# OTOsenseShield.net
KiCad netlist of a schematic drawn in EAGLE
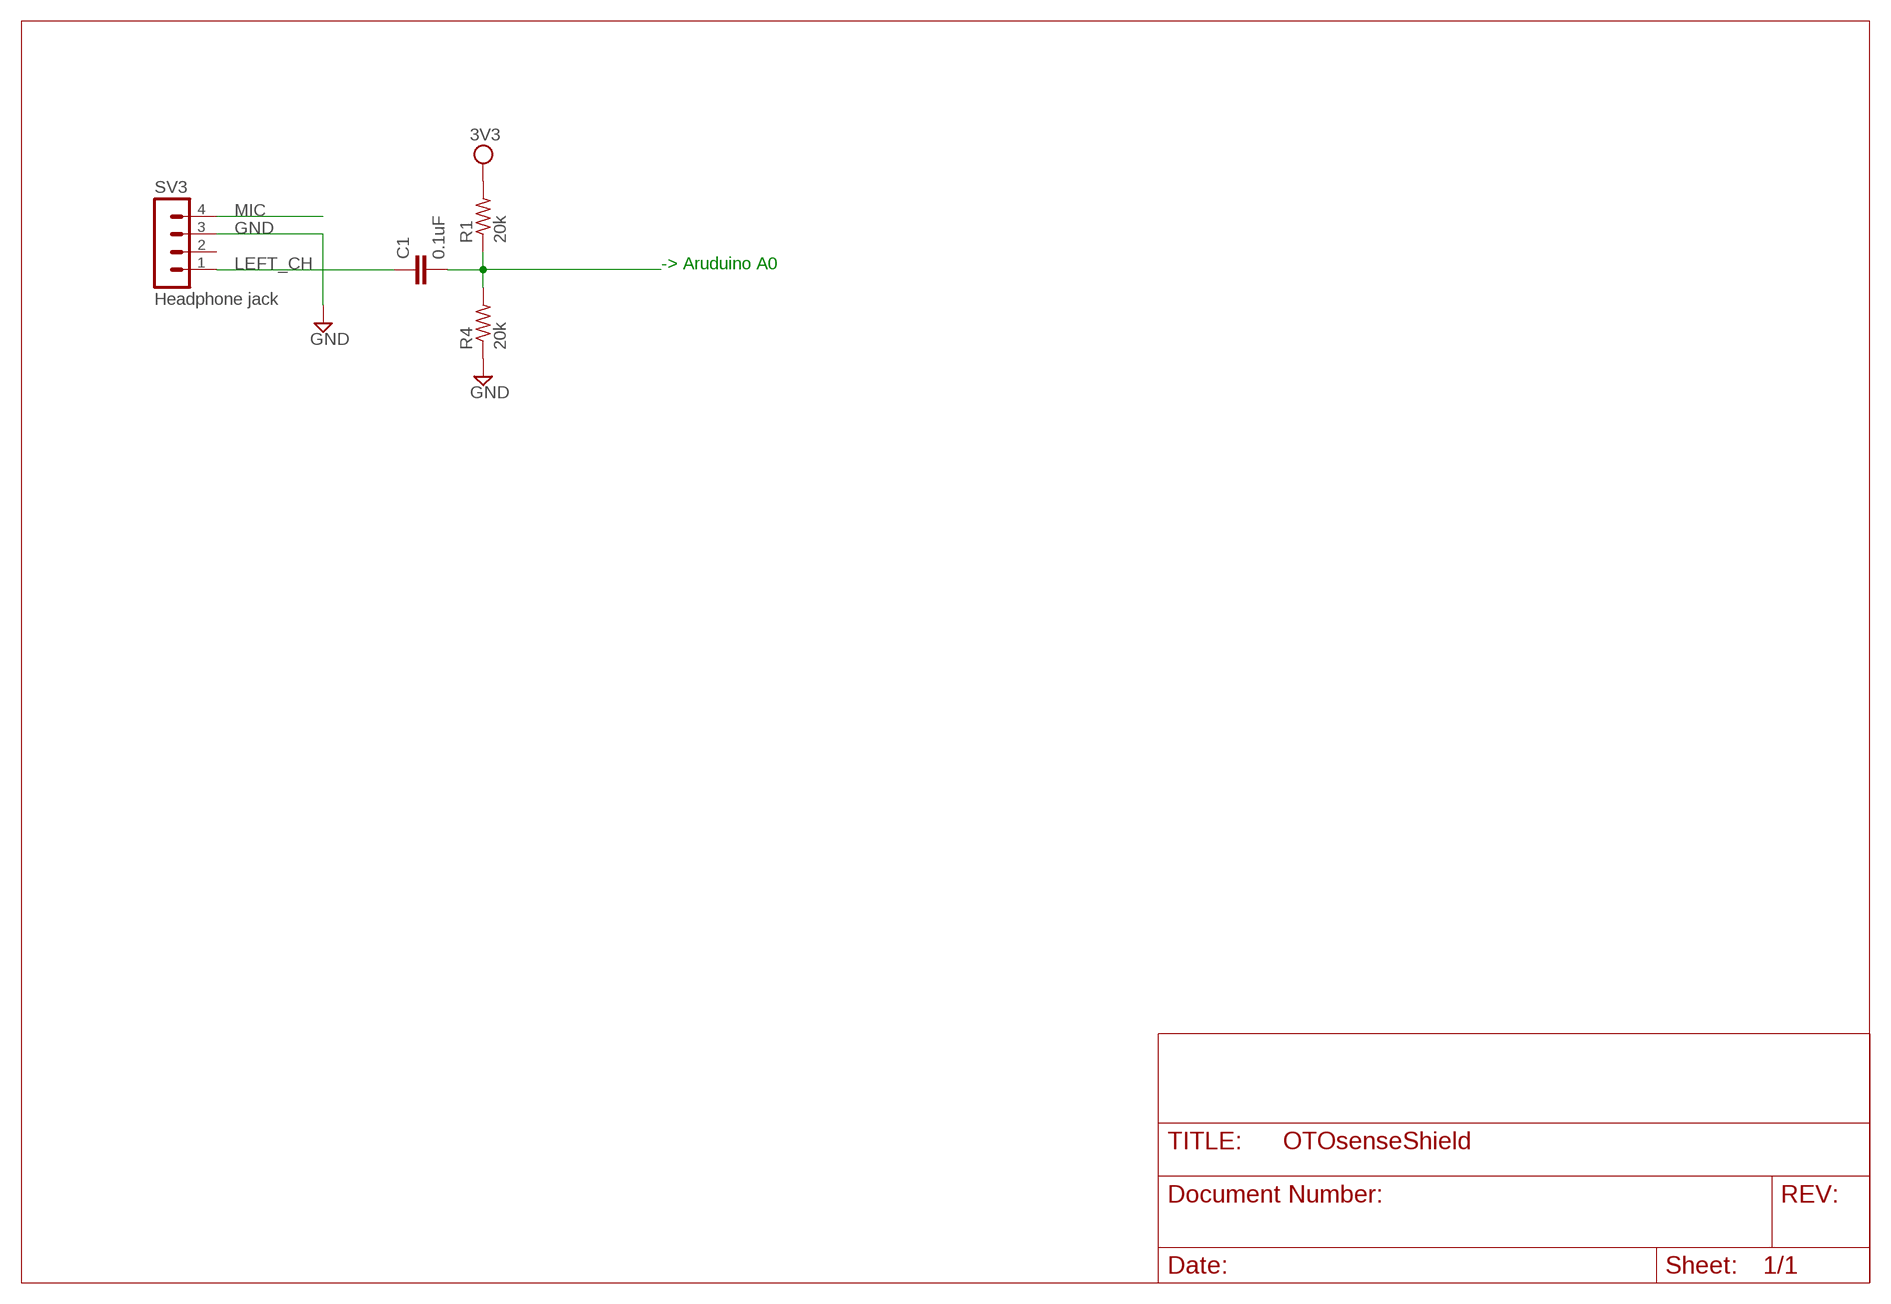
[diagram p0: schematic, sheet 1]

(export (version "E")
  (design (tool "Eeschema 10.0.6"))
  (components
    (comp (ref "C1")
      (value "0.1uF")
      (footprint "eagle-import:C025_050-035X075")
      (libsource (lib "eagle-import") (part "C-EU025_050-035X075"))
    )
    (comp (ref "R1")
      (value "20k")
      (footprint "eagle-import:0309_10")
      (libsource (lib "eagle-import") (part "R-US_0309/10"))
    )
    (comp (ref "R4")
      (value "20k")
      (footprint "eagle-import:0309_10")
      (libsource (lib "eagle-import") (part "R-US_0309/10"))
    )
    (comp (ref "SV3")
      (value "Headphone jack")
      (footprint "eagle-import:MA04-1")
      (libsource (lib "eagle-import") (part "MA04-1"))
    )
  )
  (nets
    (net (code "1") (name "/LEFT_CH") (class "Default")
      (node (ref "C1") (pin "1") (pinfunction "1_1") (pintype "passive"))
      (node (ref "SV3") (pin "1") (pinfunction "1_1") (pintype "passive"))
    )
    (net (code "2") (name "/MIC") (class "Default")
      (node (ref "SV3") (pin "4") (pinfunction "4_4") (pintype "passive"))
    )
    (net (code "3") (name "3V3") (class "Default")
      (node (ref "R1") (pin "2") (pinfunction "2_2") (pintype "passive"))
    )
    (net (code "4") (name "GND") (class "Default")
      (node (ref "R4") (pin "1") (pinfunction "1_1") (pintype "passive"))
      (node (ref "SV3") (pin "3") (pinfunction "3_3") (pintype "passive"))
    )
    (net (code "5") (name "Net-(C1-Pad2)") (class "Default")
      (node (ref "C1") (pin "2") (pinfunction "2_2") (pintype "passive"))
      (node (ref "R1") (pin "1") (pinfunction "1_1") (pintype "passive"))
      (node (ref "R4") (pin "2") (pinfunction "2_2") (pintype "passive"))
    )
    (net (code "6") (name "unconnected-(SV3-Pad2)") (class "Default")
      (node (ref "SV3") (pin "2") (pinfunction "2_2") (pintype "passive"))
    )
  )
)
